# POV3.net
KiCad netlist of a schematic drawn in EAGLE
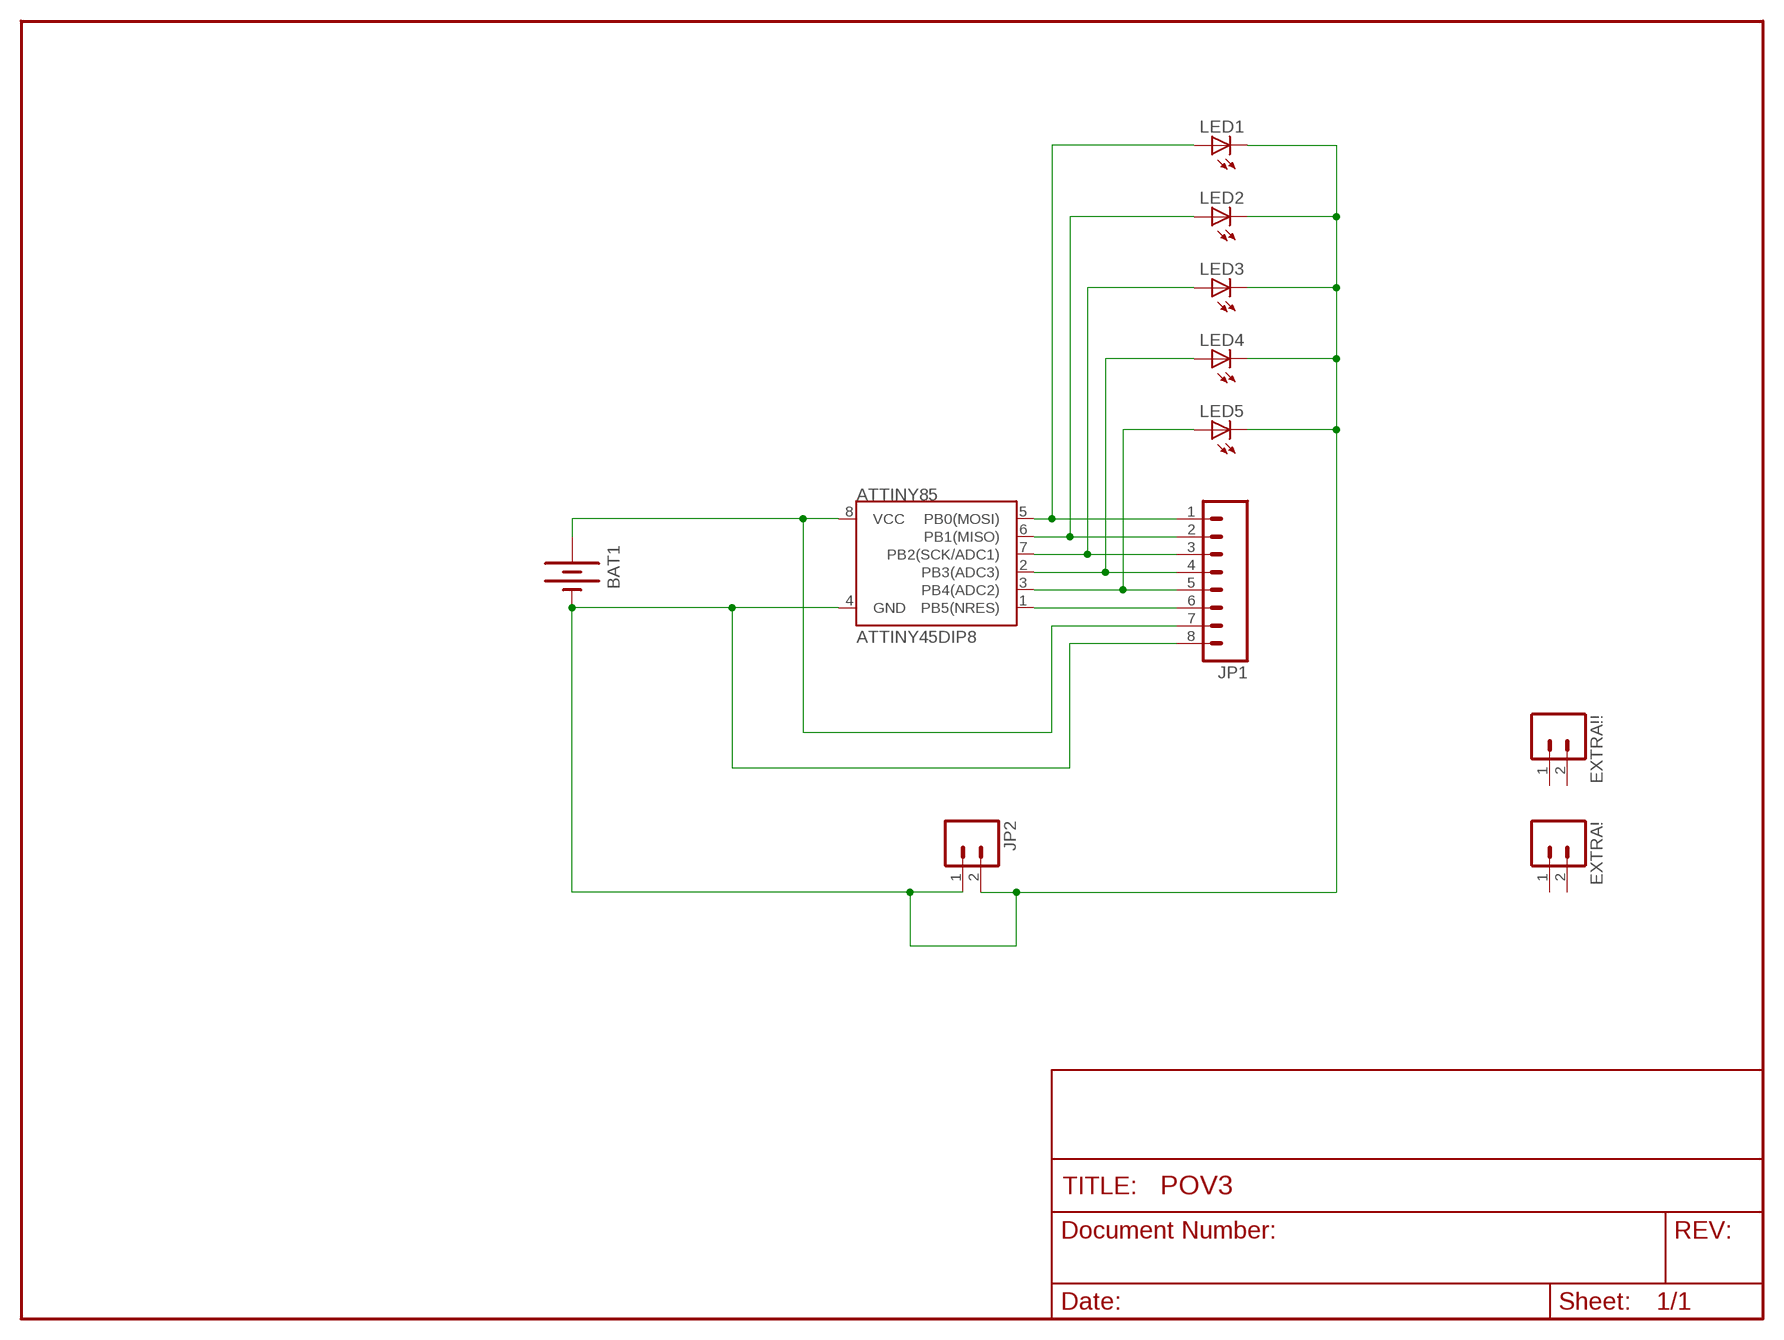
[diagram p0: schematic, sheet 1]

(export (version "E")
  (design (tool "Eeschema 10.0.6"))
  (components
    (comp (ref "ATTINY85")
      (value "ATTINY45DIP8")
      (footprint "eagle-import:DIP08")
      (libsource (lib "eagle-import") (part "ATTINY45DIP8"))
    )
    (comp (ref "BAT1")
      (value "BATTERY20PTH")
      (footprint "eagle-import:BATTCOM_20MM_PTH")
      (libsource (lib "eagle-import") (part "BATTERY20PTH"))
    )
    (comp (ref "EXTRA!")
      (value "M02PTH")
      (footprint "eagle-import:1X02")
      (libsource (lib "eagle-import") (part "M02PTH"))
    )
    (comp (ref "EXTRA!!")
      (value "M02PTH")
      (footprint "eagle-import:1X02")
      (libsource (lib "eagle-import") (part "M02PTH"))
    )
    (comp (ref "JP1")
      (value "M08")
      (footprint "eagle-import:1X08")
      (libsource (lib "eagle-import") (part "M08"))
    )
    (comp (ref "JP2")
      (value "M02PTH")
      (footprint "eagle-import:1X02")
      (libsource (lib "eagle-import") (part "M02PTH"))
    )
    (comp (ref "LED1")
      (value "LED5MM")
      (footprint "eagle-import:LED5MM")
      (libsource (lib "eagle-import") (part "LED5MM"))
    )
    (comp (ref "LED2")
      (value "LED5MM")
      (footprint "eagle-import:LED5MM")
      (libsource (lib "eagle-import") (part "LED5MM"))
    )
    (comp (ref "LED3")
      (value "LED5MM")
      (footprint "eagle-import:LED5MM")
      (libsource (lib "eagle-import") (part "LED5MM"))
    )
    (comp (ref "LED4")
      (value "LED5MM")
      (footprint "eagle-import:LED5MM")
      (libsource (lib "eagle-import") (part "LED5MM"))
    )
    (comp (ref "LED5")
      (value "LED5MM")
      (footprint "eagle-import:LED5MM")
      (libsource (lib "eagle-import") (part "LED5MM"))
    )
  )
  (nets
    (net (code "1") (name "Net-(ATTINY85-GND)") (class "Default")
      (node (ref "ATTINY85") (pin "4") (pinfunction "GND_4") (pintype "bidirectional"))
      (node (ref "BAT1") (pin "2") (pinfunction "-_2") (pintype "power_in"))
      (node (ref "JP1") (pin "8") (pinfunction "8_8") (pintype "passive"))
      (node (ref "JP2") (pin "1") (pinfunction "1_1") (pintype "passive"))
      (node (ref "JP2") (pin "2") (pinfunction "2_2") (pintype "passive"))
      (node (ref "LED1") (pin "K") (pinfunction "C_K") (pintype "passive"))
      (node (ref "LED2") (pin "K") (pinfunction "C_K") (pintype "passive"))
      (node (ref "LED3") (pin "K") (pinfunction "C_K") (pintype "passive"))
      (node (ref "LED4") (pin "K") (pinfunction "C_K") (pintype "passive"))
      (node (ref "LED5") (pin "K") (pinfunction "C_K") (pintype "passive"))
    )
    (net (code "2") (name "Net-(ATTINY85-PB0(MOSI))") (class "Default")
      (node (ref "ATTINY85") (pin "5") (pinfunction "PB0(MOSI)_5") (pintype "bidirectional"))
      (node (ref "JP1") (pin "1") (pinfunction "1_1") (pintype "passive"))
      (node (ref "LED1") (pin "A") (pinfunction "A_A") (pintype "passive"))
    )
    (net (code "3") (name "Net-(ATTINY85-PB1(MISO))") (class "Default")
      (node (ref "ATTINY85") (pin "6") (pinfunction "PB1(MISO)_6") (pintype "bidirectional"))
      (node (ref "JP1") (pin "2") (pinfunction "2_2") (pintype "passive"))
      (node (ref "LED2") (pin "A") (pinfunction "A_A") (pintype "passive"))
    )
    (net (code "4") (name "Net-(ATTINY85-PB2(SCK{slash}ADC1))") (class "Default")
      (node (ref "ATTINY85") (pin "7") (pinfunction "PB2(SCK/ADC1)_7") (pintype "bidirectional"))
      (node (ref "JP1") (pin "3") (pinfunction "3_3") (pintype "passive"))
      (node (ref "LED3") (pin "A") (pinfunction "A_A") (pintype "passive"))
    )
    (net (code "5") (name "Net-(ATTINY85-PB3(ADC3))") (class "Default")
      (node (ref "ATTINY85") (pin "2") (pinfunction "PB3(ADC3)_2") (pintype "bidirectional"))
      (node (ref "JP1") (pin "4") (pinfunction "4_4") (pintype "passive"))
      (node (ref "LED4") (pin "A") (pinfunction "A_A") (pintype "passive"))
    )
    (net (code "6") (name "Net-(ATTINY85-PB4(ADC2))") (class "Default")
      (node (ref "ATTINY85") (pin "3") (pinfunction "PB4(ADC2)_3") (pintype "bidirectional"))
      (node (ref "JP1") (pin "5") (pinfunction "5_5") (pintype "passive"))
      (node (ref "LED5") (pin "A") (pinfunction "A_A") (pintype "passive"))
    )
    (net (code "7") (name "Net-(ATTINY85-PB5(NRES))") (class "Default")
      (node (ref "ATTINY85") (pin "1") (pinfunction "PB5(NRES)_1") (pintype "bidirectional"))
      (node (ref "JP1") (pin "6") (pinfunction "6_6") (pintype "passive"))
    )
    (net (code "8") (name "Net-(ATTINY85-VCC)") (class "Default")
      (node (ref "ATTINY85") (pin "8") (pinfunction "VCC_8") (pintype "bidirectional"))
      (node (ref "BAT1") (pin "1") (pinfunction "+_1") (pintype "power_in"))
      (node (ref "JP1") (pin "7") (pinfunction "7_7") (pintype "passive"))
    )
    (net (code "9") (name "unconnected-(EXTRA!!-Pad1)") (class "Default")
      (node (ref "EXTRA!!") (pin "1") (pinfunction "1_1") (pintype "passive"))
    )
    (net (code "10") (name "unconnected-(EXTRA!!-Pad2)") (class "Default")
      (node (ref "EXTRA!!") (pin "2") (pinfunction "2_2") (pintype "passive"))
    )
    (net (code "11") (name "unconnected-(EXTRA!-Pad1)") (class "Default")
      (node (ref "EXTRA!") (pin "1") (pinfunction "1_1") (pintype "passive"))
    )
    (net (code "12") (name "unconnected-(EXTRA!-Pad2)") (class "Default")
      (node (ref "EXTRA!") (pin "2") (pinfunction "2_2") (pintype "passive"))
    )
  )
)
